# ComponentTester.net
KiCad netlist of a schematic drawn in EAGLE
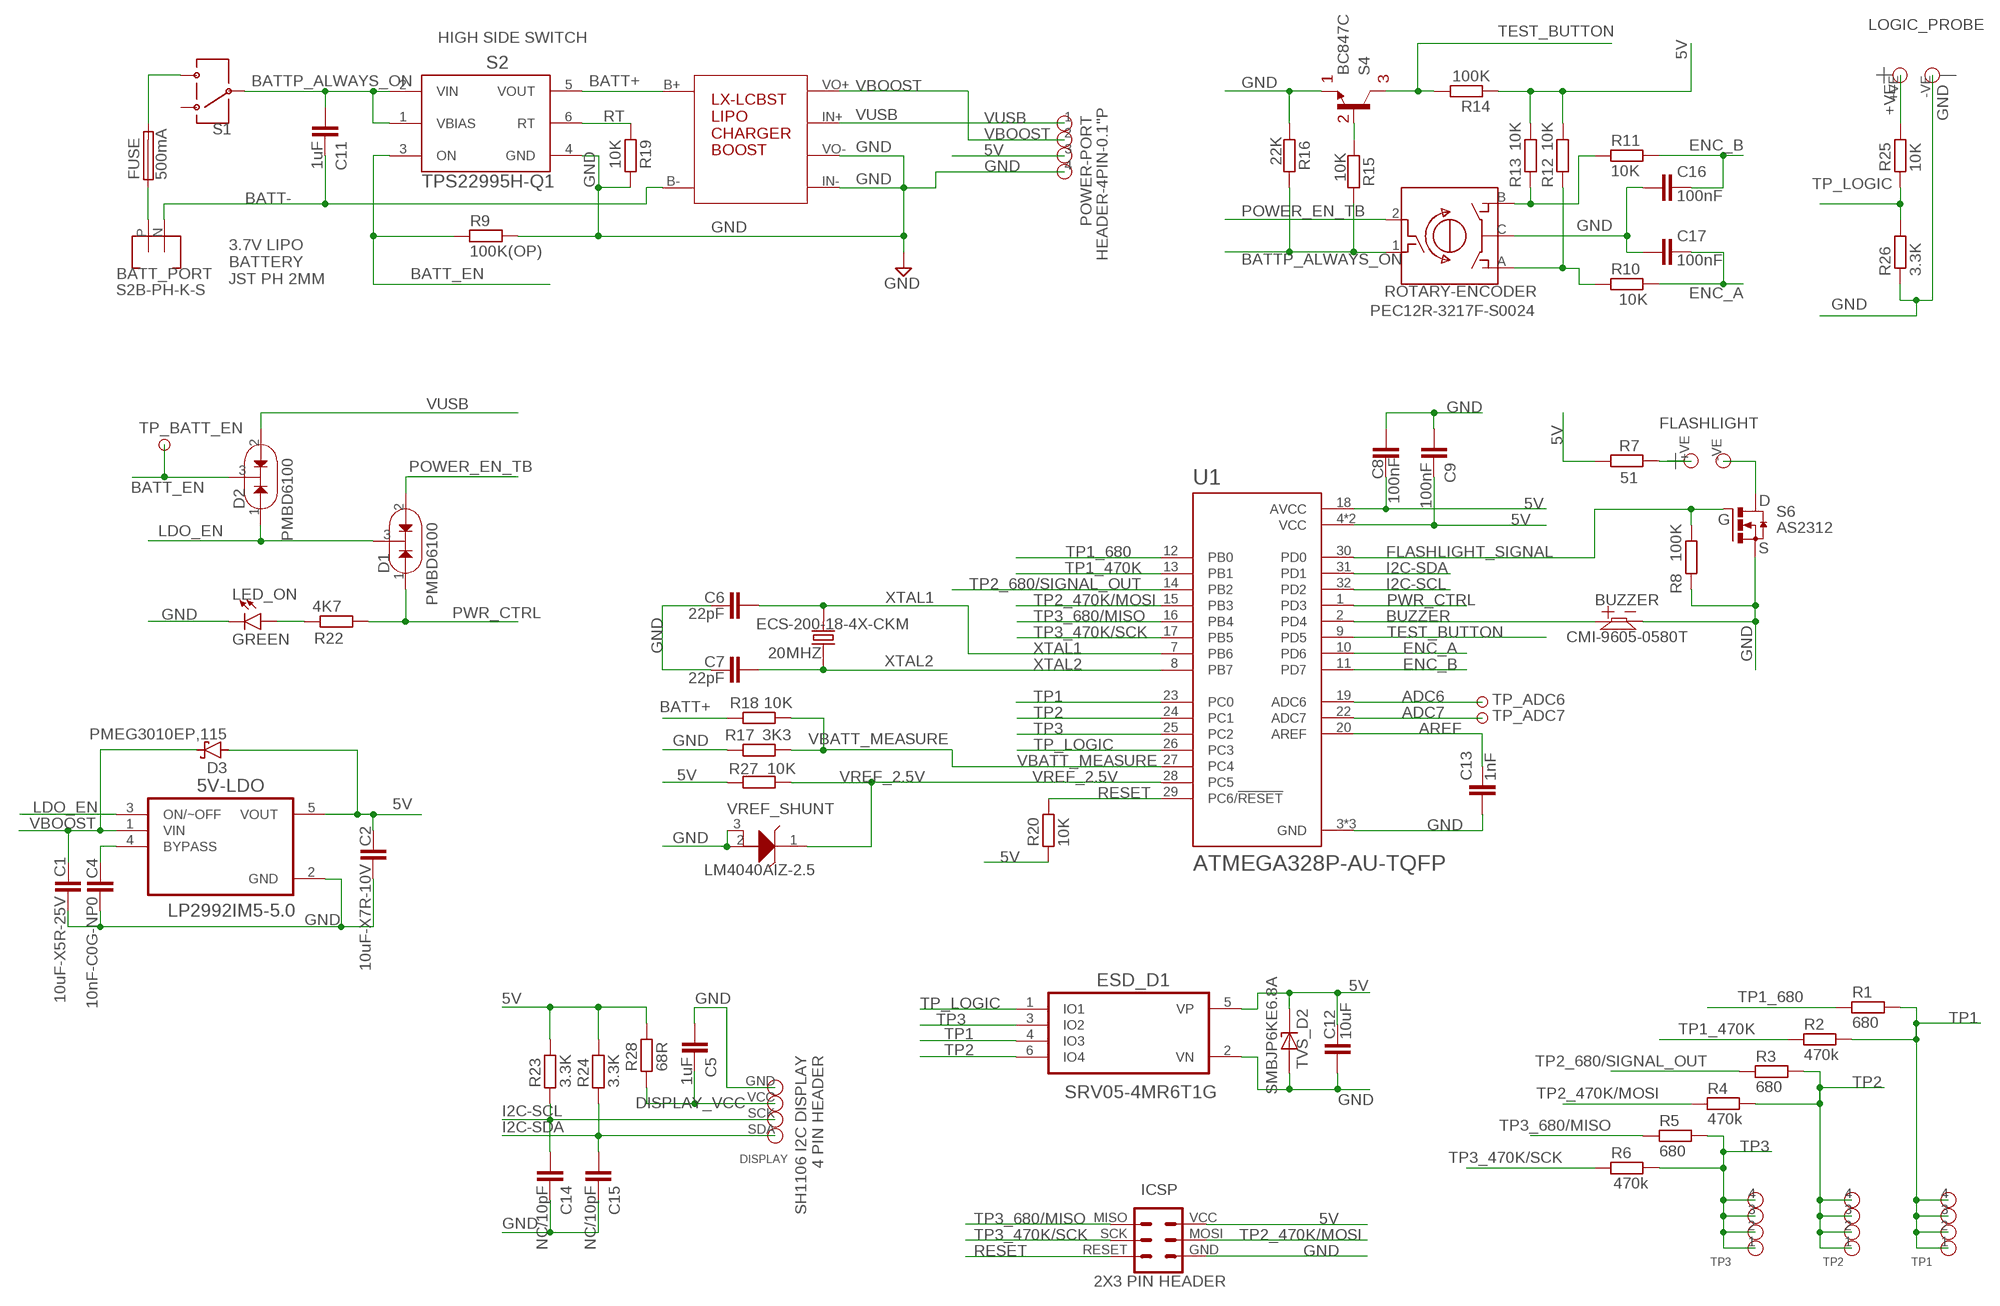
[diagram p0: schematic, sheet 1]

(export (version "E")
  (design (tool "Eeschema 10.0.6"))
  (components
    (comp (ref "5V-LDO")
      (value "LP2992IM5-5.0")
      (footprint "eagle-import:SOT-23-5")
      (fields (field (name "MF") "Texas Instruments") (field (name "MP") "LP2992IM5-5.0/NOPB"))
      (libsource (lib "eagle-import") (part "LP2992IM5-5.0"))
    )
    (comp (ref "20MHZ")
      (value "ECS-200-18-4X-CKM")
      (footprint "eagle-import:XTAL_ECS-200-18-4X-CKM")
      (fields (field (name "MF") "ECS Inc."))
      (libsource (lib "eagle-import") (part "CRYSTAL-20MHZ-ECS-200-18-4X-CKM"))
    )
    (comp (ref "BATT_PORT")
      (value "S2B-PH-K-S")
      (footprint "eagle-import:S2B-PH-K-S")
      (libsource (lib "eagle-import") (part "S2B-PH-K-S"))
    )
    (comp (ref "BUZZER")
      (value "CMI-9605-0580T")
      (footprint "eagle-import:BUZZER-ACTIVE-CMI-9605-0580T")
      (libsource (lib "eagle-import") (part "BUZZER-ACTIVE-CMI-9605-0580T"))
    )
    (comp (ref "C1")
      (value "10uF-X5R-25V")
      (footprint "eagle-import:0603")
      (libsource (lib "eagle-import") (part "CAPACITOR0603"))
    )
    (comp (ref "C2")
      (value "10uF-X7R-10V")
      (footprint "eagle-import:0603")
      (libsource (lib "eagle-import") (part "CAPACITOR0603"))
    )
    (comp (ref "C4")
      (value "10nF-C0G-NP0")
      (footprint "eagle-import:0603")
      (libsource (lib "eagle-import") (part "CAPACITOR_SMD0603"))
    )
    (comp (ref "C5")
      (value "1uF")
      (footprint "eagle-import:0603")
      (libsource (lib "eagle-import") (part "CAPACITOR_SMD0603"))
    )
    (comp (ref "C6")
      (value "22pF")
      (footprint "eagle-import:0603")
      (libsource (lib "eagle-import") (part "CAPACITOR_SMD0603"))
    )
    (comp (ref "C7")
      (value "22pF")
      (footprint "eagle-import:0603")
      (libsource (lib "eagle-import") (part "CAPACITOR_SMD0603"))
    )
    (comp (ref "C8")
      (value "100nF")
      (footprint "eagle-import:0603")
      (libsource (lib "eagle-import") (part "CAPACITOR_SMD0603"))
    )
    (comp (ref "C9")
      (value "100nF")
      (footprint "eagle-import:0603")
      (libsource (lib "eagle-import") (part "CAPACITOR_SMD0603"))
    )
    (comp (ref "C11")
      (value "1uF")
      (footprint "eagle-import:0603")
      (libsource (lib "eagle-import") (part "CAPACITOR_SMD0603"))
    )
    (comp (ref "C12")
      (value "10uF")
      (footprint "eagle-import:0603")
      (libsource (lib "eagle-import") (part "CAPACITOR_SMD0603"))
    )
    (comp (ref "C13")
      (value "1nF")
      (footprint "eagle-import:0603")
      (libsource (lib "eagle-import") (part "CAPACITOR_SMD0603"))
    )
    (comp (ref "C14")
      (value "NC/10pF")
      (footprint "eagle-import:0603")
      (libsource (lib "eagle-import") (part "CAPACITOR_SMD0603"))
    )
    (comp (ref "C15")
      (value "NC/10pF")
      (footprint "eagle-import:0603")
      (libsource (lib "eagle-import") (part "CAPACITOR_SMD0603"))
    )
    (comp (ref "C16")
      (value "100nF")
      (footprint "eagle-import:0603")
      (libsource (lib "eagle-import") (part "CAPACITOR_SMD0603"))
    )
    (comp (ref "C17")
      (value "100nF")
      (footprint "eagle-import:0603")
      (libsource (lib "eagle-import") (part "CAPACITOR_SMD0603"))
    )
    (comp (ref "CHARGE_BOOST")
      (value "BATTERY-CHARGER-BOOST-MODULE-LX-LCBST")
      (footprint "eagle-import:BATTERY-CHARGER-BOOST-MODULE-LX-LCBST")
      (libsource (lib "eagle-import") (part "BATTERY-CHARGER-BOOST-MODULE-LX-LCBST"))
    )
    (comp (ref "D1")
      (value "PMBD6100")
      (footprint "eagle-import:SOT-23-3")
      (libsource (lib "eagle-import") (part "DIODE-DOUBLE-COMMON-CATHODE-PMBD6100,215"))
    )
    (comp (ref "D2")
      (value "PMBD6100")
      (footprint "eagle-import:SOT-23-3")
      (libsource (lib "eagle-import") (part "DIODE-DOUBLE-COMMON-CATHODE-PMBD6100,215"))
    )
    (comp (ref "D3")
      (value "PMEG3010EP,115")
      (footprint "eagle-import:SOD-128")
      (libsource (lib "eagle-import") (part "DIODE-SCHOTTKY-PMEG3010EP,115"))
    )
    (comp (ref "DISPLAY")
      (value "DISPLAY-1.3\"-SH1106-I2C")
      (footprint "eagle-import:DISPLAY-1.3_-SH1106-I2C")
      (libsource (lib "eagle-import") (part "DISPLAY-1.3{dblquote}-SH1106-I2C"))
    )
    (comp (ref "ESD_D1")
      (value "SRV05-4MR6T1G")
      (footprint "eagle-import:SOT-23-6")
      (fields (field (name "MF") "ON Semiconductor"))
      (libsource (lib "eagle-import") (part "SRV05-4MR6T1G"))
    )
    (comp (ref "FLASHLIGHT")
      (value "HEADER-2PIN-0.2\"P")
      (footprint "eagle-import:HEADER-2PIN-0.2_P")
      (libsource (lib "eagle-import") (part "HEADER-2PIN-0.2{dblquote}P"))
    )
    (comp (ref "FUSE")
      (value "500mA")
      (footprint "eagle-import:1206")
      (libsource (lib "eagle-import") (part "FUSE"))
    )
    (comp (ref "ICSP")
      (value "2X3 PIN HEADER")
      (footprint "eagle-import:HEADER-ICSP-0.1_P")
      (libsource (lib "eagle-import") (part "HEADER-ICSP-0.1{dblquote}P"))
    )
    (comp (ref "LED_ON")
      (value "GREEN")
      (footprint "eagle-import:1206-DIODE")
      (libsource (lib "eagle-import") (part "LED1206"))
    )
    (comp (ref "LOGIC_PROBE")
      (value "HEADER-2PIN-0.2\"P-LOGIC-PROBE")
      (footprint "eagle-import:HEADER-2PIN-0.2_P-LOGIC-PROBE")
      (libsource (lib "eagle-import") (part "HEADER-2PIN-0.2{dblquote}P-LOGIC-PROBE"))
    )
    (comp (ref "POWER-PORT")
      (value "HEADER-4PIN-0.1\"P")
      (footprint "eagle-import:HEADER-4PIN-0.1_P")
      (libsource (lib "eagle-import") (part "HEADER-4PIN-0.1{dblquote}P"))
    )
    (comp (ref "R1")
      (value "680")
      (footprint "eagle-import:1206")
      (libsource (lib "eagle-import") (part "RESISTOR_SMD1206"))
    )
    (comp (ref "R2")
      (value "470k")
      (footprint "eagle-import:1206")
      (libsource (lib "eagle-import") (part "RESISTOR_SMD1206"))
    )
    (comp (ref "R3")
      (value "680")
      (footprint "eagle-import:1206")
      (libsource (lib "eagle-import") (part "RESISTOR_SMD1206"))
    )
    (comp (ref "R4")
      (value "470k")
      (footprint "eagle-import:1206")
      (libsource (lib "eagle-import") (part "RESISTOR_SMD1206"))
    )
    (comp (ref "R5")
      (value "680")
      (footprint "eagle-import:1206")
      (libsource (lib "eagle-import") (part "RESISTOR_SMD1206"))
    )
    (comp (ref "R6")
      (value "470k")
      (footprint "eagle-import:1206")
      (libsource (lib "eagle-import") (part "RESISTOR_SMD1206"))
    )
    (comp (ref "R7")
      (value "51")
      (footprint "eagle-import:1206")
      (libsource (lib "eagle-import") (part "RESISTOR_SMD1206"))
    )
    (comp (ref "R8")
      (value "100K")
      (footprint "eagle-import:0603")
      (libsource (lib "eagle-import") (part "RESISTOR_SMD0603"))
    )
    (comp (ref "R9")
      (value "100K(OP)")
      (footprint "eagle-import:0603")
      (libsource (lib "eagle-import") (part "RESISTOR_SMD0603"))
    )
    (comp (ref "R10")
      (value "10K")
      (footprint "eagle-import:0603")
      (libsource (lib "eagle-import") (part "RESISTOR_SMD0603"))
    )
    (comp (ref "R11")
      (value "10K")
      (footprint "eagle-import:0603")
      (libsource (lib "eagle-import") (part "RESISTOR_SMD0603"))
    )
    (comp (ref "R12")
      (value "10K")
      (footprint "eagle-import:0603")
      (libsource (lib "eagle-import") (part "RESISTOR_SMD0603"))
    )
    (comp (ref "R13")
      (value "10K")
      (footprint "eagle-import:0603")
      (libsource (lib "eagle-import") (part "RESISTOR_SMD0603"))
    )
    (comp (ref "R14")
      (value "100K")
      (footprint "eagle-import:0603")
      (libsource (lib "eagle-import") (part "RESISTOR_SMD0603"))
    )
    (comp (ref "R15")
      (value "10K")
      (footprint "eagle-import:0603")
      (libsource (lib "eagle-import") (part "RESISTOR_SMD0603"))
    )
    (comp (ref "R16")
      (value "22K")
      (footprint "eagle-import:0603")
      (libsource (lib "eagle-import") (part "RESISTOR_SMD0603"))
    )
    (comp (ref "R17")
      (value "3K3")
      (footprint "eagle-import:0603")
      (libsource (lib "eagle-import") (part "RESISTOR_SMD0603"))
    )
    (comp (ref "R18")
      (value "10K")
      (footprint "eagle-import:0603")
      (libsource (lib "eagle-import") (part "RESISTOR_SMD0603"))
    )
    (comp (ref "R19")
      (value "10K")
      (footprint "eagle-import:0603")
      (libsource (lib "eagle-import") (part "RESISTOR_SMD0603"))
    )
    (comp (ref "R20")
      (value "10K")
      (footprint "eagle-import:0603")
      (libsource (lib "eagle-import") (part "RESISTOR_SMD0603"))
    )
    (comp (ref "R22")
      (value "4K7")
      (footprint "eagle-import:0603")
      (libsource (lib "eagle-import") (part "RESISTOR_SMD0603"))
    )
    (comp (ref "R23")
      (value "3.3K")
      (footprint "eagle-import:0603")
      (libsource (lib "eagle-import") (part "RESISTOR_SMD0603"))
    )
    (comp (ref "R24")
      (value "3.3K")
      (footprint "eagle-import:0603")
      (libsource (lib "eagle-import") (part "RESISTOR_SMD0603"))
    )
    (comp (ref "R25")
      (value "10K")
      (footprint "eagle-import:0603")
      (libsource (lib "eagle-import") (part "RESISTOR_SMD0603"))
    )
    (comp (ref "R26")
      (value "3.3K")
      (footprint "eagle-import:0603")
      (libsource (lib "eagle-import") (part "RESISTOR_SMD0603"))
    )
    (comp (ref "R27")
      (value "10K")
      (footprint "eagle-import:0603")
      (libsource (lib "eagle-import") (part "RESISTOR_SMD0603"))
    )
    (comp (ref "R28")
      (value "68R")
      (footprint "eagle-import:0603")
      (libsource (lib "eagle-import") (part "RESISTOR_SMD0603"))
    )
    (comp (ref "ROTARY-ENCODER")
      (value "PEC12R-3217F-S0024")
      (footprint "eagle-import:PEC12R-3217F-S0024")
      (libsource (lib "eagle-import") (part "PEC12R-3217F-S0024"))
    )
    (comp (ref "S1")
      (value "SLW-913535-2A-RA-D")
      (footprint "eagle-import:SLW-913535-2A-RA-D")
      (libsource (lib "eagle-import") (part "SLW-913535-2A-RA-D"))
    )
    (comp (ref "S2")
      (value "TPS22995H-Q1")
      (footprint "eagle-import:SOT-23-6")
      (libsource (lib "eagle-import") (part "TPS22995H-Q1"))
    )
    (comp (ref "S4")
      (value "BC847C")
      (footprint "eagle-import:SOT-23-3")
      (libsource (lib "eagle-import") (part "BC847C"))
    )
    (comp (ref "S6")
      (value "AS2312")
      (footprint "eagle-import:SOT-23-3")
      (libsource (lib "eagle-import") (part "AS2312AS2312"))
    )
    (comp (ref "TP1")
      (value "HEADER-4PIN-0.1\"P")
      (footprint "eagle-import:HEADER-4PIN-0.1_P")
      (libsource (lib "eagle-import") (part "HEADER-4PIN-0.1{dblquote}P"))
    )
    (comp (ref "TP2")
      (value "HEADER-4PIN-0.1\"P")
      (footprint "eagle-import:HEADER-4PIN-0.1_P")
      (libsource (lib "eagle-import") (part "HEADER-4PIN-0.1{dblquote}P"))
    )
    (comp (ref "TP3")
      (value "HEADER-4PIN-0.1\"P")
      (footprint "eagle-import:HEADER-4PIN-0.1_P")
      (libsource (lib "eagle-import") (part "HEADER-4PIN-0.1{dblquote}P"))
    )
    (comp (ref "TP_ADC6")
      (value "TEST-POINT-TH")
      (footprint "eagle-import:TEST-POINT-TH-1MM")
      (libsource (lib "eagle-import") (part "TEST-POINT-TH"))
    )
    (comp (ref "TP_ADC7")
      (value "TEST-POINT-TH")
      (footprint "eagle-import:TEST-POINT-TH-1MM")
      (libsource (lib "eagle-import") (part "TEST-POINT-TH"))
    )
    (comp (ref "TP_BATT_EN")
      (value "TEST-POINT-SMD")
      (footprint "eagle-import:TEST-POINT-SMD-1MM")
      (libsource (lib "eagle-import") (part "TEST-POINT-SMD"))
    )
    (comp (ref "TVS_D2")
      (value "SMBJP6KE6.8A")
      (footprint "eagle-import:DIOM5336X244N")
      (fields
        (field (name "DIGIKEY_PART_NUMBER") "SMBJP6KE6.8A-TPMSTR-ND")
        (field (name "MF") "Micro Commercial")
        (field (name "MP") "SMBJP6KE6.8A-TP")
      )
      (libsource (lib "eagle-import") (part "SMBJP6KE6.8A-TP"))
    )
    (comp (ref "U1")
      (value "ATMEGA328P-AU-TQFP")
      (footprint "eagle-import:TQFP32")
      (fields (field (name "MF") "Microchip") (field (name "MP") "ATMEGA328P-AU"))
      (libsource (lib "eagle-import") (part "ATMEGA328P-AU-TQFP"))
    )
    (comp (ref "VREF_SHUNT")
      (value "LM4040AIZ-2.5")
      (footprint "eagle-import:SOT-23-3")
      (libsource (lib "eagle-import") (part "LM4040AELT-2.5-SOT23"))
    )
  )
  (nets
    (net (code "1") (name "/+VE") (class "Default")
      (node (ref "LOGIC_PROBE") (pin "+VE") (pinfunction "P$1_+VE") (pintype "bidirectional"))
      (node (ref "R25") (pin "2") (pinfunction "2_2") (pintype "passive"))
    )
    (net (code "2") (name "/5V") (class "Default")
      (node (ref "5V-LDO") (pin "5") (pinfunction "VOUT_5") (pintype "output"))
      (node (ref "C12") (pin "1") (pinfunction "1_1") (pintype "passive"))
      (node (ref "C2") (pin "2") (pinfunction "2_2") (pintype "passive"))
      (node (ref "C8") (pin "2") (pinfunction "2_2") (pintype "passive"))
      (node (ref "C9") (pin "1") (pinfunction "1_1") (pintype "passive"))
      (node (ref "D3") (pin "A") (pinfunction "A_A") (pintype "passive"))
      (node (ref "ESD_D1") (pin "5") (pinfunction "VP_5") (pintype "power_in"))
      (node (ref "ICSP") (pin "VCC") (pinfunction "2_VCC") (pintype "passive"))
      (node (ref "POWER-PORT") (pin "3") (pinfunction "P$3_3") (pintype "bidirectional"))
      (node (ref "R12") (pin "2") (pinfunction "2_2") (pintype "passive"))
      (node (ref "R13") (pin "2") (pinfunction "2_2") (pintype "passive"))
      (node (ref "R14") (pin "1") (pinfunction "1_1") (pintype "passive"))
      (node (ref "R20") (pin "1") (pinfunction "1_1") (pintype "passive"))
      (node (ref "R23") (pin "2") (pinfunction "2_2") (pintype "passive"))
      (node (ref "R24") (pin "2") (pinfunction "2_2") (pintype "passive"))
      (node (ref "R27") (pin "1") (pinfunction "1_1") (pintype "passive"))
      (node (ref "R28") (pin "2") (pinfunction "2_2") (pintype "passive"))
      (node (ref "R7") (pin "1") (pinfunction "1_1") (pintype "passive"))
      (node (ref "TVS_D2") (pin "C") (pinfunction "C_C") (pintype "passive"))
      (node (ref "U1") (pin "18") (pinfunction "AVCC_18") (pintype "power_in"))
      (node (ref "U1") (pin "4") (pinfunction "VCC_4") (pintype "power_in"))
      (node (ref "U1") (pin "6") (pinfunction "VCC_6") (pintype "power_in"))
    )
    (net (code "3") (name "/ADC6") (class "Default")
      (node (ref "TP_ADC6") (pin "P$1") (pinfunction "P$1_P$1") (pintype "bidirectional"))
      (node (ref "U1") (pin "19") (pinfunction "ADC6_19") (pintype "bidirectional"))
    )
    (net (code "4") (name "/ADC7") (class "Default")
      (node (ref "TP_ADC7") (pin "P$1") (pinfunction "P$1_P$1") (pintype "bidirectional"))
      (node (ref "U1") (pin "22") (pinfunction "ADC7_22") (pintype "bidirectional"))
    )
    (net (code "5") (name "/AREF") (class "Default")
      (node (ref "C13") (pin "1") (pinfunction "1_1") (pintype "passive"))
      (node (ref "U1") (pin "20") (pinfunction "AREF_20") (pintype "input"))
    )
    (net (code "6") (name "/BATT+") (class "Default")
      (node (ref "CHARGE_BOOST") (pin "B+") (pinfunction "B+_B+") (pintype "bidirectional"))
      (node (ref "R18") (pin "2") (pinfunction "2_2") (pintype "passive"))
      (node (ref "S2") (pin "5") (pinfunction "VOUT_5") (pintype "output"))
    )
    (net (code "7") (name "/BATT-") (class "Default")
      (node (ref "BATT_PORT") (pin "N") (pinfunction "N_N") (pintype "bidirectional"))
      (node (ref "C11") (pin "1") (pinfunction "1_1") (pintype "passive"))
      (node (ref "CHARGE_BOOST") (pin "B-") (pinfunction "B-_B-") (pintype "bidirectional"))
    )
    (net (code "8") (name "/BATTP_ALWAYS_ON") (class "Default")
      (node (ref "C11") (pin "2") (pinfunction "2_2") (pintype "passive"))
      (node (ref "ROTARY-ENCODER") (pin "2") (pinfunction "2_2") (pintype "bidirectional"))
      (node (ref "S1") (pin "2") (pinfunction "2_2") (pintype "bidirectional"))
      (node (ref "S2") (pin "1") (pinfunction "VBIAS_1") (pintype "output"))
      (node (ref "S2") (pin "2") (pinfunction "VIN_2") (pintype "input"))
    )
    (net (code "9") (name "/BATT_EN") (class "Default")
      (node (ref "D2") (pin "3") (pinfunction "C_3") (pintype "bidirectional"))
      (node (ref "R9") (pin "1") (pinfunction "1_1") (pintype "passive"))
      (node (ref "S2") (pin "3") (pinfunction "ON_3") (pintype "input"))
      (node (ref "TP_BATT_EN") (pin "P$1") (pinfunction "P$1_P$1") (pintype "bidirectional"))
    )
    (net (code "10") (name "/BUZZER") (class "Default")
      (node (ref "BUZZER") (pin "P$1") (pinfunction "P$1_P$1") (pintype "bidirectional"))
      (node (ref "U1") (pin "2") (pinfunction "PD4_2") (pintype "bidirectional"))
    )
    (net (code "11") (name "/DISPLAY_VCC") (class "Default")
      (node (ref "C5") (pin "1") (pinfunction "1_1") (pintype "passive"))
      (node (ref "DISPLAY") (pin "VCC") (pinfunction "VCC_VCC") (pintype "bidirectional"))
      (node (ref "R28") (pin "1") (pinfunction "1_1") (pintype "passive"))
    )
    (net (code "12") (name "/ENC_A") (class "Default")
      (node (ref "C17") (pin "1") (pinfunction "1_1") (pintype "passive"))
      (node (ref "R10") (pin "2") (pinfunction "2_2") (pintype "passive"))
      (node (ref "U1") (pin "10") (pinfunction "PD6_10") (pintype "bidirectional"))
    )
    (net (code "13") (name "/ENC_B") (class "Default")
      (node (ref "C16") (pin "1") (pinfunction "1_1") (pintype "passive"))
      (node (ref "R11") (pin "2") (pinfunction "2_2") (pintype "passive"))
      (node (ref "U1") (pin "11") (pinfunction "PD7_11") (pintype "bidirectional"))
    )
    (net (code "14") (name "/FLASHLIGHT_SIGNAL") (class "Default")
      (node (ref "R8") (pin "1") (pinfunction "1_1") (pintype "passive"))
      (node (ref "S6") (pin "1") (pinfunction "G_1") (pintype "passive"))
      (node (ref "U1") (pin "30") (pinfunction "PD0_30") (pintype "bidirectional"))
    )
    (net (code "15") (name "/I2C-SCL") (class "Default")
      (node (ref "C14") (pin "2") (pinfunction "2_2") (pintype "passive"))
      (node (ref "DISPLAY") (pin "SCK") (pinfunction "SCK_SCK") (pintype "bidirectional"))
      (node (ref "R23") (pin "1") (pinfunction "1_1") (pintype "passive"))
      (node (ref "U1") (pin "32") (pinfunction "PD2_32") (pintype "bidirectional"))
    )
    (net (code "16") (name "/I2C-SDA") (class "Default")
      (node (ref "C15") (pin "2") (pinfunction "2_2") (pintype "passive"))
      (node (ref "DISPLAY") (pin "SDA") (pinfunction "SDA_SDA") (pintype "bidirectional"))
      (node (ref "R24") (pin "1") (pinfunction "1_1") (pintype "passive"))
      (node (ref "U1") (pin "31") (pinfunction "PD1_31") (pintype "bidirectional"))
    )
    (net (code "17") (name "/LDO_EN") (class "Default")
      (node (ref "5V-LDO") (pin "3") (pinfunction "ON/~{OFF}_3") (pintype "input"))
      (node (ref "D1") (pin "3") (pinfunction "C_3") (pintype "bidirectional"))
      (node (ref "D2") (pin "1") (pinfunction "A1_1") (pintype "bidirectional"))
    )
    (net (code "18") (name "/POWER_EN_TB") (class "Default")
      (node (ref "D1") (pin "2") (pinfunction "A2_2") (pintype "bidirectional"))
      (node (ref "R15") (pin "2") (pinfunction "2_2") (pintype "passive"))
      (node (ref "R16") (pin "2") (pinfunction "2_2") (pintype "passive"))
      (node (ref "ROTARY-ENCODER") (pin "1") (pinfunction "1_1") (pintype "bidirectional"))
    )
    (net (code "19") (name "/PWR_CTRL") (class "Default")
      (node (ref "D1") (pin "1") (pinfunction "A1_1") (pintype "bidirectional"))
      (node (ref "R22") (pin "2") (pinfunction "2_2") (pintype "passive"))
      (node (ref "U1") (pin "1") (pinfunction "PD3_1") (pintype "bidirectional"))
    )
    (net (code "20") (name "/RESET") (class "Default")
      (node (ref "ICSP") (pin "RESET") (pinfunction "5_RESET") (pintype "passive"))
      (node (ref "R20") (pin "2") (pinfunction "2_2") (pintype "passive"))
      (node (ref "U1") (pin "29") (pinfunction "PC6/~{RESET}_29") (pintype "bidirectional"))
    )
    (net (code "21") (name "/RT") (class "Default")
      (node (ref "R19") (pin "1") (pinfunction "1_1") (pintype "passive"))
      (node (ref "S2") (pin "6") (pinfunction "RT_6") (pintype "output"))
    )
    (net (code "22") (name "/TEST_BUTTON") (class "Default")
      (node (ref "R14") (pin "2") (pinfunction "2_2") (pintype "passive"))
      (node (ref "S4") (pin "3") (pinfunction "C_3") (pintype "passive"))
      (node (ref "U1") (pin "9") (pinfunction "PD5_9") (pintype "bidirectional"))
    )
    (net (code "23") (name "/TP1") (class "Default")
      (node (ref "ESD_D1") (pin "4") (pinfunction "IO3_4") (pintype "input"))
      (node (ref "R1") (pin "2") (pinfunction "2_2") (pintype "passive"))
      (node (ref "R2") (pin "2") (pinfunction "2_2") (pintype "passive"))
      (node (ref "TP1") (pin "1") (pinfunction "P$1_1") (pintype "bidirectional"))
      (node (ref "TP1") (pin "2") (pinfunction "P$2_2") (pintype "bidirectional"))
      (node (ref "TP1") (pin "3") (pinfunction "P$3_3") (pintype "bidirectional"))
      (node (ref "TP1") (pin "4") (pinfunction "P$4_4") (pintype "bidirectional"))
      (node (ref "U1") (pin "23") (pinfunction "PC0_23") (pintype "bidirectional"))
    )
    (net (code "24") (name "/TP1_470K") (class "Default")
      (node (ref "R2") (pin "1") (pinfunction "1_1") (pintype "passive"))
      (node (ref "U1") (pin "13") (pinfunction "PB1_13") (pintype "bidirectional"))
    )
    (net (code "25") (name "/TP1_680") (class "Default")
      (node (ref "R1") (pin "1") (pinfunction "1_1") (pintype "passive"))
      (node (ref "U1") (pin "12") (pinfunction "PB0_12") (pintype "bidirectional"))
    )
    (net (code "26") (name "/TP2") (class "Default")
      (node (ref "ESD_D1") (pin "6") (pinfunction "IO4_6") (pintype "input"))
      (node (ref "R3") (pin "2") (pinfunction "2_2") (pintype "passive"))
      (node (ref "R4") (pin "2") (pinfunction "2_2") (pintype "passive"))
      (node (ref "TP2") (pin "1") (pinfunction "P$1_1") (pintype "bidirectional"))
      (node (ref "TP2") (pin "2") (pinfunction "P$2_2") (pintype "bidirectional"))
      (node (ref "TP2") (pin "3") (pinfunction "P$3_3") (pintype "bidirectional"))
      (node (ref "TP2") (pin "4") (pinfunction "P$4_4") (pintype "bidirectional"))
      (node (ref "U1") (pin "24") (pinfunction "PC1_24") (pintype "bidirectional"))
    )
    (net (code "27") (name "/TP2_470K{slash}MOSI") (class "Default")
      (node (ref "ICSP") (pin "MOSI") (pinfunction "4_MOSI") (pintype "passive"))
      (node (ref "R4") (pin "1") (pinfunction "1_1") (pintype "passive"))
      (node (ref "U1") (pin "15") (pinfunction "PB3_15") (pintype "bidirectional"))
    )
    (net (code "28") (name "/TP2_680{slash}SIGNAL_OUT") (class "Default")
      (node (ref "R3") (pin "1") (pinfunction "1_1") (pintype "passive"))
      (node (ref "U1") (pin "14") (pinfunction "PB2_14") (pintype "bidirectional"))
    )
    (net (code "29") (name "/TP3") (class "Default")
      (node (ref "ESD_D1") (pin "3") (pinfunction "IO2_3") (pintype "input"))
      (node (ref "R5") (pin "2") (pinfunction "2_2") (pintype "passive"))
      (node (ref "R6") (pin "2") (pinfunction "2_2") (pintype "passive"))
      (node (ref "TP3") (pin "1") (pinfunction "P$1_1") (pintype "bidirectional"))
      (node (ref "TP3") (pin "2") (pinfunction "P$2_2") (pintype "bidirectional"))
      (node (ref "TP3") (pin "3") (pinfunction "P$3_3") (pintype "bidirectional"))
      (node (ref "TP3") (pin "4") (pinfunction "P$4_4") (pintype "bidirectional"))
      (node (ref "U1") (pin "25") (pinfunction "PC2_25") (pintype "bidirectional"))
    )
    (net (code "30") (name "/TP3_470K{slash}SCK") (class "Default")
      (node (ref "ICSP") (pin "SCK") (pinfunction "3_SCK") (pintype "passive"))
      (node (ref "R6") (pin "1") (pinfunction "1_1") (pintype "passive"))
      (node (ref "U1") (pin "17") (pinfunction "PB5_17") (pintype "bidirectional"))
    )
    (net (code "31") (name "/TP3_680{slash}MISO") (class "Default")
      (node (ref "ICSP") (pin "MISO") (pinfunction "1_MISO") (pintype "passive"))
      (node (ref "R5") (pin "1") (pinfunction "1_1") (pintype "passive"))
      (node (ref "U1") (pin "16") (pinfunction "PB4_16") (pintype "bidirectional"))
    )
    (net (code "32") (name "/TP_LOGIC") (class "Default")
      (node (ref "ESD_D1") (pin "1") (pinfunction "IO1_1") (pintype "input"))
      (node (ref "R25") (pin "1") (pinfunction "1_1") (pintype "passive"))
      (node (ref "R26") (pin "2") (pinfunction "2_2") (pintype "passive"))
      (node (ref "U1") (pin "26") (pinfunction "PC3_26") (pintype "bidirectional"))
    )
    (net (code "33") (name "/VBATT_MEASURE") (class "Default")
      (node (ref "R17") (pin "2") (pinfunction "2_2") (pintype "passive"))
      (node (ref "R18") (pin "1") (pinfunction "1_1") (pintype "passive"))
      (node (ref "U1") (pin "27") (pinfunction "PC4_27") (pintype "bidirectional"))
    )
    (net (code "34") (name "/VBOOST") (class "Default")
      (node (ref "5V-LDO") (pin "1") (pinfunction "VIN_1") (pintype "input"))
      (node (ref "C1") (pin "2") (pinfunction "2_2") (pintype "passive"))
      (node (ref "CHARGE_BOOST") (pin "VO+") (pinfunction "VO+_VO+") (pintype "bidirectional"))
      (node (ref "D3") (pin "K") (pinfunction "C_K") (pintype "passive"))
      (node (ref "POWER-PORT") (pin "2") (pinfunction "P$2_2") (pintype "bidirectional"))
    )
    (net (code "35") (name "/VREF_2.5V") (class "Default")
      (node (ref "R27") (pin "2") (pinfunction "2_2") (pintype "passive"))
      (node (ref "U1") (pin "28") (pinfunction "PC5_28") (pintype "bidirectional"))
      (node (ref "VREF_SHUNT") (pin "1") (pinfunction "C_1") (pintype "bidirectional"))
    )
    (net (code "36") (name "/VUSB") (class "Default")
      (node (ref "CHARGE_BOOST") (pin "IN+") (pinfunction "USB+_IN+") (pintype "bidirectional"))
      (node (ref "D2") (pin "2") (pinfunction "A2_2") (pintype "bidirectional"))
      (node (ref "POWER-PORT") (pin "1") (pinfunction "P$1_1") (pintype "bidirectional"))
    )
    (net (code "37") (name "/XTAL1") (class "Default")
      (node (ref "20MHZ") (pin "2") (pinfunction "2_2") (pintype "passive"))
      (node (ref "C6") (pin "2") (pinfunction "2_2") (pintype "passive"))
      (node (ref "U1") (pin "7") (pinfunction "PB6_7") (pintype "bidirectional"))
    )
    (net (code "38") (name "/XTAL2") (class "Default")
      (node (ref "20MHZ") (pin "1") (pinfunction "1_1") (pintype "passive"))
      (node (ref "C7") (pin "2") (pinfunction "2_2") (pintype "passive"))
      (node (ref "U1") (pin "8") (pinfunction "PB7_8") (pintype "bidirectional"))
    )
    (net (code "39") (name "GND") (class "Default")
      (node (ref "5V-LDO") (pin "2") (pinfunction "GND_2") (pintype "power_in"))
      (node (ref "BUZZER") (pin "P$2") (pinfunction "P$2_P$2") (pintype "bidirectional"))
      (node (ref "C1") (pin "1") (pinfunction "1_1") (pintype "passive"))
      (node (ref "C12") (pin "2") (pinfunction "2_2") (pintype "passive"))
      (node (ref "C13") (pin "2") (pinfunction "2_2") (pintype "passive"))
      (node (ref "C14") (pin "1") (pinfunction "1_1") (pintype "passive"))
      (node (ref "C15") (pin "1") (pinfunction "1_1") (pintype "passive"))
      (node (ref "C16") (pin "2") (pinfunction "2_2") (pintype "passive"))
      (node (ref "C17") (pin "2") (pinfunction "2_2") (pintype "passive"))
      (node (ref "C2") (pin "1") (pinfunction "1_1") (pintype "passive"))
      (node (ref "C4") (pin "1") (pinfunction "1_1") (pintype "passive"))
      (node (ref "C5") (pin "2") (pinfunction "2_2") (pintype "passive"))
      (node (ref "C6") (pin "1") (pinfunction "1_1") (pintype "passive"))
      (node (ref "C7") (pin "1") (pinfunction "1_1") (pintype "passive"))
      (node (ref "C8") (pin "1") (pinfunction "1_1") (pintype "passive"))
      (node (ref "C9") (pin "2") (pinfunction "2_2") (pintype "passive"))
      (node (ref "CHARGE_BOOST") (pin "IN-") (pinfunction "USB-_IN-") (pintype "bidirectional"))
      (node (ref "CHARGE_BOOST") (pin "VO-") (pinfunction "VO-_VO-") (pintype "bidirectional"))
      (node (ref "DISPLAY") (pin "GND") (pinfunction "GND_GND") (pintype "bidirectional"))
      (node (ref "ESD_D1") (pin "2") (pinfunction "VN_2") (pintype "power_in"))
      (node (ref "ICSP") (pin "GND") (pinfunction "6_GND") (pintype "passive"))
      (node (ref "LED_ON") (pin "C") (pinfunction "C_C") (pintype "passive"))
      (node (ref "LOGIC_PROBE") (pin "-VE") (pinfunction "P$2_-VE") (pintype "bidirectional"))
      (node (ref "POWER-PORT") (pin "4") (pinfunction "P$4_4") (pintype "bidirectional"))
      (node (ref "R16") (pin "1") (pinfunction "1_1") (pintype "passive"))
      (node (ref "R17") (pin "1") (pinfunction "1_1") (pintype "passive"))
      (node (ref "R19") (pin "2") (pinfunction "2_2") (pintype "passive"))
      (node (ref "R26") (pin "1") (pinfunction "1_1") (pintype "passive"))
      (node (ref "R8") (pin "2") (pinfunction "2_2") (pintype "passive"))
      (node (ref "R9") (pin "2") (pinfunction "2_2") (pintype "passive"))
      (node (ref "ROTARY-ENCODER") (pin "C") (pinfunction "C_C") (pintype "bidirectional"))
      (node (ref "S2") (pin "4") (pinfunction "GND_4") (pintype "power_in"))
      (node (ref "S4") (pin "2") (pinfunction "E_2") (pintype "passive"))
      (node (ref "S6") (pin "2") (pinfunction "S_2") (pintype "passive"))
      (node (ref "TVS_D2") (pin "A") (pinfunction "A_A") (pintype "passive"))
      (node (ref "U1") (pin "21") (pinfunction "GND_21") (pintype "power_in"))
      (node (ref "U1") (pin "3") (pinfunction "GND_3") (pintype "power_in"))
      (node (ref "U1") (pin "5") (pinfunction "GND_5") (pintype "power_in"))
      (node (ref "VREF_SHUNT") (pin "2") (pinfunction "A_2") (pintype "bidirectional"))
      (node (ref "VREF_SHUNT") (pin "3") (pinfunction "NC/A_3") (pintype "bidirectional"))
    )
    (net (code "40") (name "Net-(5V-LDO-BYPASS)") (class "Default")
      (node (ref "5V-LDO") (pin "4") (pinfunction "BYPASS_4") (pintype "input"))
      (node (ref "C4") (pin "2") (pinfunction "2_2") (pintype "passive"))
    )
    (net (code "41") (name "Net-(BATT_PORT-PadP)") (class "Default")
      (node (ref "BATT_PORT") (pin "P") (pinfunction "P_P") (pintype "bidirectional"))
      (node (ref "FUSE") (pin "1") (pinfunction "1_1") (pintype "passive"))
    )
    (net (code "42") (name "Net-(FLASHLIGHT-P$1)") (class "Default")
      (node (ref "FLASHLIGHT") (pin "+VE") (pinfunction "P$1_+VE") (pintype "bidirectional"))
      (node (ref "R7") (pin "2") (pinfunction "2_2") (pintype "passive"))
    )
    (net (code "43") (name "Net-(FLASHLIGHT-P$2)") (class "Default")
      (node (ref "FLASHLIGHT") (pin "-VE") (pinfunction "P$2_-VE") (pintype "bidirectional"))
      (node (ref "S6") (pin "3") (pinfunction "D_3") (pintype "passive"))
    )
    (net (code "44") (name "Net-(FUSE-Pad2)") (class "Default")
      (node (ref "FUSE") (pin "2") (pinfunction "2_2") (pintype "passive"))
      (node (ref "S1") (pin "3") (pinfunction "3_3") (pintype "bidirectional"))
    )
    (net (code "45") (name "Net-(LED_ON-PadA)") (class "Default")
      (node (ref "LED_ON") (pin "A") (pinfunction "A_A") (pintype "passive"))
      (node (ref "R22") (pin "1") (pinfunction "1_1") (pintype "passive"))
    )
    (net (code "46") (name "Net-(R10-Pad1)") (class "Default")
      (node (ref "R10") (pin "1") (pinfunction "1_1") (pintype "passive"))
      (node (ref "R12") (pin "1") (pinfunction "1_1") (pintype "passive"))
      (node (ref "ROTARY-ENCODER") (pin "A") (pinfunction "A_A") (pintype "bidirectional"))
    )
    (net (code "47") (name "Net-(R11-Pad1)") (class "Default")
      (node (ref "R11") (pin "1") (pinfunction "1_1") (pintype "passive"))
      (node (ref "R13") (pin "1") (pinfunction "1_1") (pintype "passive"))
      (node (ref "ROTARY-ENCODER") (pin "B") (pinfunction "B_B") (pintype "bidirectional"))
    )
    (net (code "48") (name "Net-(S4-B)") (class "Default")
      (node (ref "R15") (pin "1") (pinfunction "1_1") (pintype "passive"))
      (node (ref "S4") (pin "1") (pinfunction "B_1") (pintype "passive"))
    )
    (net (code "49") (name "unconnected-(S1-Pad1)") (class "Default")
      (node (ref "S1") (pin "1") (pinfunction "1_1") (pintype "bidirectional"))
    )
  )
)
